# M_M_meteo_RJ11.net
KiCad netlist of a schematic drawn in EAGLE
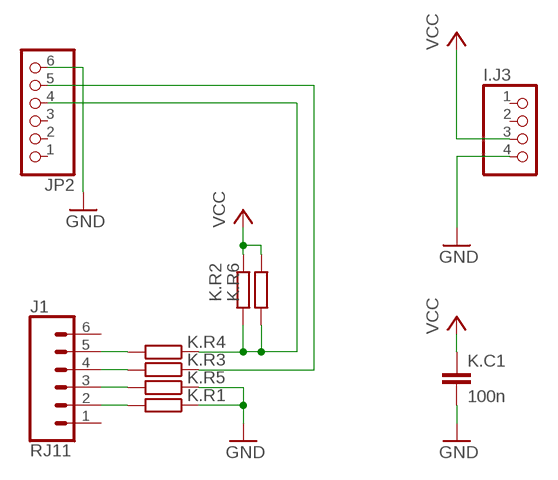
[diagram p0: schematic, sheet 1]

(export (version "E")
  (design (tool "Eeschema 10.0.6"))
  (components
    (comp (ref "I.J3")
      (value "PINHD-1X4")
      (footprint "eagle-import:1X04")
      (libsource (lib "eagle-import") (part "PINHD-1X4"))
    )
    (comp (ref "J1")
      (value "RJ11")
      (footprint "eagle-import:RJ11-6")
      (libsource (lib "eagle-import") (part "RJ11-6"))
    )
    (comp (ref "JP2")
      (value "PINHD-1X6")
      (footprint "eagle-import:1X06")
      (libsource (lib "eagle-import") (part "PINHD-1X6"))
    )
    (comp (ref "K.C1")
      (value "100n")
      (footprint "eagle-import:C0603")
      (libsource (lib "eagle-import") (part "C-EUC0603"))
    )
    (comp (ref "K.R1")
      (value "1k")
      (footprint "eagle-import:R0603")
      (libsource (lib "eagle-import") (part "R-EU_R0603"))
    )
    (comp (ref "K.R2")
      (value "4k7")
      (footprint "eagle-import:R0603")
      (libsource (lib "eagle-import") (part "R-EU_R0603"))
    )
    (comp (ref "K.R3")
      (value "1k")
      (footprint "eagle-import:R0603")
      (libsource (lib "eagle-import") (part "R-EU_R0603"))
    )
    (comp (ref "K.R4")
      (value "1k")
      (footprint "eagle-import:R0603")
      (libsource (lib "eagle-import") (part "R-EU_R0603"))
    )
    (comp (ref "K.R5")
      (value "1k")
      (footprint "eagle-import:R0603")
      (libsource (lib "eagle-import") (part "R-EU_R0603"))
    )
    (comp (ref "K.R6")
      (value "4k7")
      (footprint "eagle-import:R0603")
      (libsource (lib "eagle-import") (part "R-EU_R0603"))
    )
  )
  (nets
    (net (code "1") (name "GND") (class "Default")
      (node (ref "I.J3") (pin "4") (pinfunction "4_4") (pintype "passive"))
      (node (ref "JP2") (pin "6") (pinfunction "6_6") (pintype "passive"))
      (node (ref "K.C1") (pin "2") (pinfunction "2_2") (pintype "passive"))
      (node (ref "K.R1") (pin "1") (pinfunction "1_1") (pintype "passive"))
      (node (ref "K.R5") (pin "1") (pinfunction "1_1") (pintype "passive"))
    )
    (net (code "2") (name "Net-(J1-Pad2)") (class "Default")
      (node (ref "J1") (pin "2") (pinfunction "2_2") (pintype "passive"))
      (node (ref "K.R1") (pin "2") (pinfunction "2_2") (pintype "passive"))
    )
    (net (code "3") (name "Net-(J1-Pad3)") (class "Default")
      (node (ref "J1") (pin "3") (pinfunction "3_3") (pintype "passive"))
      (node (ref "K.R5") (pin "2") (pinfunction "2_2") (pintype "passive"))
    )
    (net (code "4") (name "Net-(J1-Pad4)") (class "Default")
      (node (ref "J1") (pin "4") (pinfunction "4_4") (pintype "passive"))
      (node (ref "K.R3") (pin "2") (pinfunction "2_2") (pintype "passive"))
    )
    (net (code "5") (name "Net-(J1-Pad5)") (class "Default")
      (node (ref "J1") (pin "5") (pinfunction "5_5") (pintype "passive"))
      (node (ref "K.R4") (pin "2") (pinfunction "2_2") (pintype "passive"))
    )
    (net (code "6") (name "Net-(JP2-Pad4)") (class "Default")
      (node (ref "JP2") (pin "4") (pinfunction "4_4") (pintype "passive"))
      (node (ref "K.R2") (pin "2") (pinfunction "2_2") (pintype "passive"))
      (node (ref "K.R4") (pin "1") (pinfunction "1_1") (pintype "passive"))
      (node (ref "K.R6") (pin "2") (pinfunction "2_2") (pintype "passive"))
    )
    (net (code "7") (name "Net-(JP2-Pad5)") (class "Default")
      (node (ref "JP2") (pin "5") (pinfunction "5_5") (pintype "passive"))
      (node (ref "K.R3") (pin "1") (pinfunction "1_1") (pintype "passive"))
    )
    (net (code "8") (name "VCC") (class "Default")
      (node (ref "I.J3") (pin "3") (pinfunction "3_3") (pintype "passive"))
      (node (ref "K.C1") (pin "1") (pinfunction "1_1") (pintype "passive"))
      (node (ref "K.R2") (pin "1") (pinfunction "1_1") (pintype "passive"))
      (node (ref "K.R6") (pin "1") (pinfunction "1_1") (pintype "passive"))
    )
    (net (code "9") (name "unconnected-(I.J3-Pad1)") (class "Default")
      (node (ref "I.J3") (pin "1") (pinfunction "1_1") (pintype "passive"))
    )
    (net (code "10") (name "unconnected-(I.J3-Pad2)") (class "Default")
      (node (ref "I.J3") (pin "2") (pinfunction "2_2") (pintype "passive"))
    )
    (net (code "11") (name "unconnected-(J1-Pad1)") (class "Default")
      (node (ref "J1") (pin "1") (pinfunction "1_1") (pintype "passive"))
    )
    (net (code "12") (name "unconnected-(J1-Pad6)") (class "Default")
      (node (ref "J1") (pin "6") (pinfunction "6_6") (pintype "passive"))
    )
    (net (code "13") (name "unconnected-(JP2-Pad1)") (class "Default")
      (node (ref "JP2") (pin "1") (pinfunction "1_1") (pintype "passive"))
    )
    (net (code "14") (name "unconnected-(JP2-Pad2)") (class "Default")
      (node (ref "JP2") (pin "2") (pinfunction "2_2") (pintype "passive"))
    )
    (net (code "15") (name "unconnected-(JP2-Pad3)") (class "Default")
      (node (ref "JP2") (pin "3") (pinfunction "3_3") (pintype "passive"))
    )
  )
)
